# test_schem.net
KiCad netlist of a schematic drawn in EAGLE
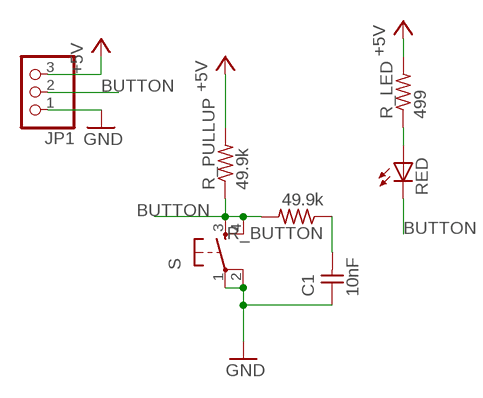
[diagram p0: schematic, sheet 1]

(export (version "E")
  (design (tool "Eeschema 10.0.6"))
  (components
    (comp (ref "C1")
      (value "10nF")
      (footprint "eagle-import:C1206FAB")
      (libsource (lib "eagle-import") (part "CAP-UNPOLARIZEDFAB"))
    )
    (comp (ref "JP1")
      (value "PINHD-1X3")
      (footprint "eagle-import:1X03")
      (libsource (lib "eagle-import") (part "PINHD-1X3"))
    )
    (comp (ref "RED")
      (value "LEDFAB1206")
      (footprint "eagle-import:LED1206FAB")
      (libsource (lib "eagle-import") (part "LEDFAB1206"))
    )
    (comp (ref "R_BUTTON")
      (value "49.9k")
      (footprint "eagle-import:R1206FAB")
      (libsource (lib "eagle-import") (part "RES-US1206FAB"))
    )
    (comp (ref "R_LED")
      (value "499")
      (footprint "eagle-import:R1206FAB")
      (libsource (lib "eagle-import") (part "RES-US1206FAB"))
    )
    (comp (ref "R_PULLUP")
      (value "49.9k")
      (footprint "eagle-import:R1206FAB")
      (libsource (lib "eagle-import") (part "RES-US1206FAB"))
    )
    (comp (ref "S")
      (value "6MM_SWITCH6MM_SWITCH")
      (footprint "eagle-import:6MM_SWITCH")
      (libsource (lib "eagle-import") (part "6MM_SWITCH6MM_SWITCH"))
    )
  )
  (nets
    (net (code "1") (name "+5V") (class "Default")
      (node (ref "JP1") (pin "3") (pinfunction "3_3") (pintype "passive"))
      (node (ref "R_LED") (pin "2") (pinfunction "2_2") (pintype "passive"))
      (node (ref "R_PULLUP") (pin "2") (pinfunction "2_2") (pintype "passive"))
    )
    (net (code "2") (name "/BUTTON") (class "Default")
      (node (ref "JP1") (pin "2") (pinfunction "2_2") (pintype "passive"))
      (node (ref "RED") (pin "2") (pinfunction "C_2") (pintype "passive"))
      (node (ref "R_BUTTON") (pin "2") (pinfunction "2_2") (pintype "passive"))
      (node (ref "R_PULLUP") (pin "1") (pinfunction "1_1") (pintype "passive"))
      (node (ref "S") (pin "3") (pinfunction "S_3") (pintype "passive"))
      (node (ref "S") (pin "4") (pinfunction "S1_4") (pintype "passive"))
    )
    (net (code "3") (name "GND") (class "Default")
      (node (ref "C1") (pin "1") (pinfunction "1_1") (pintype "passive"))
      (node (ref "JP1") (pin "1") (pinfunction "1_1") (pintype "passive"))
      (node (ref "S") (pin "1") (pinfunction "P_1") (pintype "passive"))
      (node (ref "S") (pin "2") (pinfunction "P1_2") (pintype "passive"))
    )
    (net (code "4") (name "Net-(C1-Pad2)") (class "Default")
      (node (ref "C1") (pin "2") (pinfunction "2_2") (pintype "passive"))
      (node (ref "R_BUTTON") (pin "1") (pinfunction "1_1") (pintype "passive"))
    )
    (net (code "5") (name "Net-(RED-A)") (class "Default")
      (node (ref "RED") (pin "1") (pinfunction "A_1") (pintype "passive"))
      (node (ref "R_LED") (pin "1") (pinfunction "1_1") (pintype "passive"))
    )
  )
)
